# USB-PS2.net
KiCad netlist of a schematic drawn in EAGLE
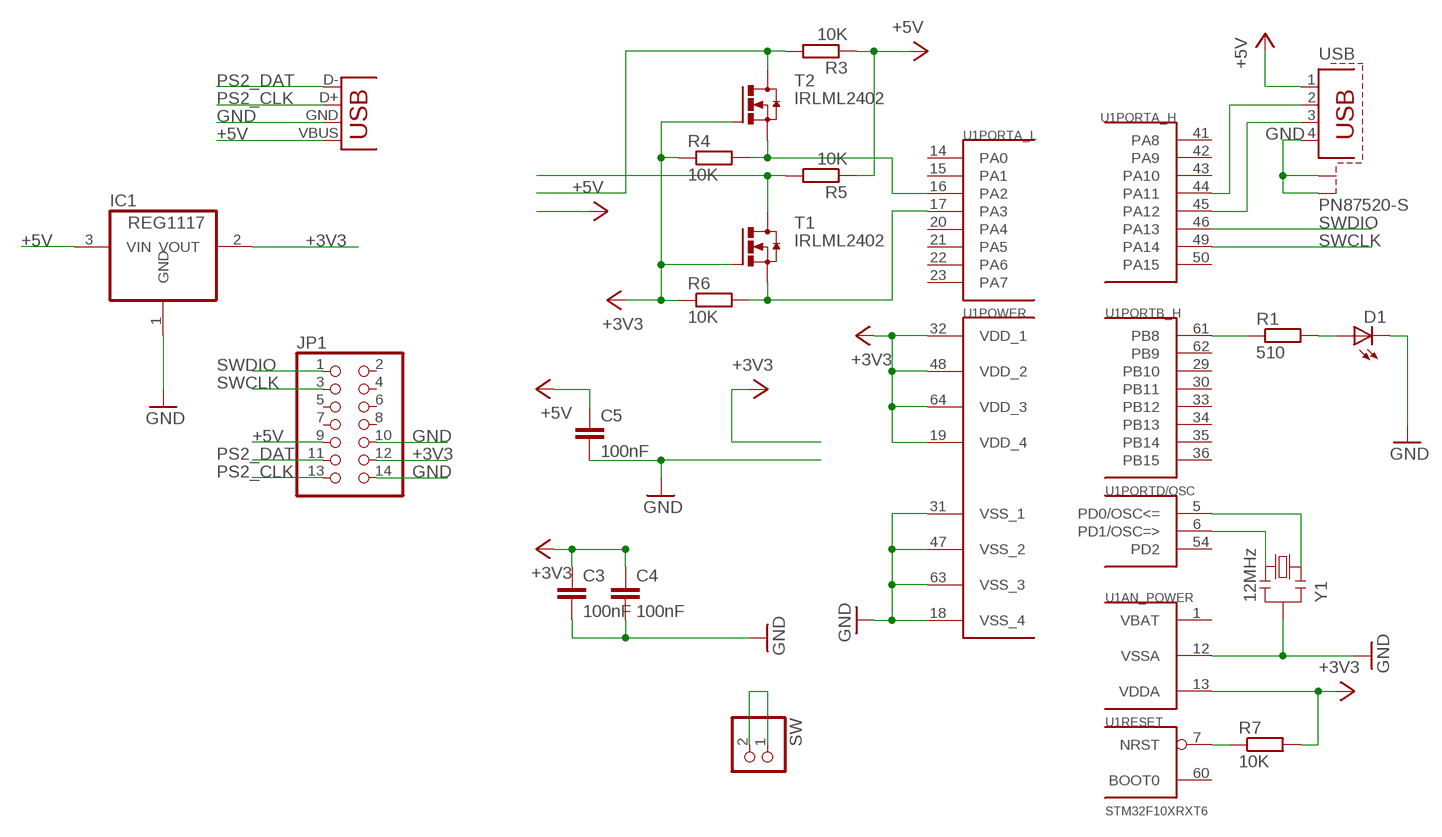
[diagram p0: schematic, sheet 1]

(export (version "E")
  (design (tool "Eeschema 10.0.6"))
  (components
    (comp (ref "C3")
      (value "100nF")
      (footprint "eagle-import:C0805")
      (libsource (lib "eagle-import") (part "C-EUC0805"))
    )
    (comp (ref "C4")
      (value "100nF")
      (footprint "eagle-import:C0805")
      (libsource (lib "eagle-import") (part "C-EUC0805"))
    )
    (comp (ref "C5")
      (value "100nF")
      (footprint "eagle-import:C0805")
      (libsource (lib "eagle-import") (part "C-EUC0805"))
    )
    (comp (ref "D1")
      (value "LEDSML0805")
      (footprint "eagle-import:SML0805")
      (libsource (lib "eagle-import") (part "LEDSML0805"))
    )
    (comp (ref "IC1")
      (value "REG1117")
      (footprint "eagle-import:SOT223")
      (libsource (lib "eagle-import") (part "REG1117"))
    )
    (comp (ref "JP1")
      (value "PINHD-2X7")
      (footprint "eagle-import:2X07")
      (libsource (lib "eagle-import") (part "PINHD-2X7"))
    )
    (comp (ref "R1")
      (value "510")
      (footprint "eagle-import:R0805")
      (libsource (lib "eagle-import") (part "R-EU_R0805"))
    )
    (comp (ref "R3")
      (value "10K")
      (footprint "eagle-import:R0805")
      (libsource (lib "eagle-import") (part "R-EU_R0805"))
    )
    (comp (ref "R4")
      (value "10K")
      (footprint "eagle-import:R0805")
      (libsource (lib "eagle-import") (part "R-EU_R0805"))
    )
    (comp (ref "R5")
      (value "10K")
      (footprint "eagle-import:R0805")
      (libsource (lib "eagle-import") (part "R-EU_R0805"))
    )
    (comp (ref "R6")
      (value "10K")
      (footprint "eagle-import:R0805")
      (libsource (lib "eagle-import") (part "R-EU_R0805"))
    )
    (comp (ref "R7")
      (value "10K")
      (footprint "eagle-import:R0805")
      (libsource (lib "eagle-import") (part "R-EU_R0805"))
    )
    (comp (ref "SW")
      (value "PINHD-1X2")
      (footprint "eagle-import:1X02")
      (libsource (lib "eagle-import") (part "PINHD-1X2"))
    )
    (comp (ref "T1")
      (value "IRLML2402")
      (footprint "eagle-import:MICRO3")
      (libsource (lib "eagle-import") (part "IRLML2402"))
    )
    (comp (ref "T2")
      (value "IRLML2402")
      (footprint "eagle-import:MICRO3")
      (libsource (lib "eagle-import") (part "IRLML2402"))
    )
    (comp (ref "U1")
      (value "STM32F10XRXT6")
      (footprint "eagle-import:TQFP64")
      (libsource (lib "eagle-import") (part "STM32F10XRXT6"))
    )
    (comp (ref "USB")
      (value "PN87520-S")
      (footprint "eagle-import:PN87520-S")
      (libsource (lib "eagle-import") (part "PN87520-S"))
    )
    (comp (ref "X1")
      (value "USB-A-H")
      (footprint "eagle-import:USB-A-H")
      (libsource (lib "eagle-import") (part "USB-A-H"))
    )
    (comp (ref "Y1")
      (value "12MHz")
      (footprint "eagle-import:RESONATOR")
      (fields (field (name "PART_NUMBER") "CSTCE16M0V53-R0"))
      (libsource (lib "eagle-import") (part "0011_CSTCE16M0V53-R0"))
    )
  )
  (nets
    (net (code "1") (name "+3V3") (class "Default")
      (node (ref "C3") (pin "1") (pinfunction "1_1") (pintype "passive"))
      (node (ref "C4") (pin "1") (pinfunction "1_1") (pintype "passive"))
      (node (ref "IC1") (pin "2") (pinfunction "VOUT_2") (pintype "output"))
      (node (ref "JP1") (pin "12") (pinfunction "12_12") (pintype "passive"))
      (node (ref "R4") (pin "1") (pinfunction "1_1") (pintype "passive"))
      (node (ref "R6") (pin "1") (pinfunction "1_1") (pintype "passive"))
      (node (ref "R7") (pin "2") (pinfunction "2_2") (pintype "passive"))
      (node (ref "T1") (pin "1") (pinfunction "G_1") (pintype "passive"))
      (node (ref "T2") (pin "1") (pinfunction "G_1") (pintype "passive"))
      (node (ref "U1") (pin "13") (pinfunction "VDDA_13") (pintype "power_in"))
      (node (ref "U1") (pin "19") (pinfunction "VDD_4_19") (pintype "power_in"))
      (node (ref "U1") (pin "32") (pinfunction "VDD_1_32") (pintype "power_in"))
      (node (ref "U1") (pin "48") (pinfunction "VDD_2_48") (pintype "power_in"))
      (node (ref "U1") (pin "64") (pinfunction "VDD_3_64") (pintype "power_in"))
    )
    (net (code "2") (name "+5V") (class "Default")
      (node (ref "C5") (pin "1") (pinfunction "1_1") (pintype "passive"))
      (node (ref "IC1") (pin "3") (pinfunction "VIN_3") (pintype "input"))
      (node (ref "JP1") (pin "9") (pinfunction "9_9") (pintype "passive"))
      (node (ref "R3") (pin "1") (pinfunction "1_1") (pintype "passive"))
      (node (ref "R5") (pin "1") (pinfunction "1_1") (pintype "passive"))
      (node (ref "USB") (pin "1") (pinfunction "1_1") (pintype "passive"))
      (node (ref "X1") (pin "VBUS") (pinfunction "GND_VBUS") (pintype "bidirectional"))
    )
    (net (code "3") (name "/PS2_CLK") (class "Default")
      (node (ref "JP1") (pin "13") (pinfunction "13_13") (pintype "passive"))
      (node (ref "R5") (pin "2") (pinfunction "2_2") (pintype "passive"))
      (node (ref "T1") (pin "3") (pinfunction "D_3") (pintype "passive"))
      (node (ref "X1") (pin "D+") (pinfunction "D-_D+") (pintype "bidirectional"))
    )
    (net (code "4") (name "/PS2_DAT") (class "Default")
      (node (ref "JP1") (pin "11") (pinfunction "11_11") (pintype "passive"))
      (node (ref "R3") (pin "2") (pinfunction "2_2") (pintype "passive"))
      (node (ref "T2") (pin "3") (pinfunction "D_3") (pintype "passive"))
      (node (ref "X1") (pin "D-") (pinfunction "D+_D-") (pintype "bidirectional"))
    )
    (net (code "5") (name "/SWCLK") (class "Default")
      (node (ref "JP1") (pin "3") (pinfunction "3_3") (pintype "passive"))
      (node (ref "U1") (pin "49") (pinfunction "PA14_49") (pintype "bidirectional"))
    )
    (net (code "6") (name "/SWDIO") (class "Default")
      (node (ref "JP1") (pin "1") (pinfunction "1_1") (pintype "passive"))
      (node (ref "U1") (pin "46") (pinfunction "PA13_46") (pintype "bidirectional"))
    )
    (net (code "7") (name "/VBAT") (class "Default")
      (node (ref "U1") (pin "1") (pinfunction "VBAT_1") (pintype "power_in"))
    )
    (net (code "8") (name "GND") (class "Default")
      (node (ref "C3") (pin "2") (pinfunction "2_2") (pintype "passive"))
      (node (ref "C4") (pin "2") (pinfunction "2_2") (pintype "passive"))
      (node (ref "C5") (pin "2") (pinfunction "2_2") (pintype "passive"))
      (node (ref "D1") (pin "C") (pinfunction "C_C") (pintype "passive"))
      (node (ref "IC1") (pin "1") (pinfunction "GND_1") (pintype "power_in"))
      (node (ref "JP1") (pin "10") (pinfunction "10_10") (pintype "passive"))
      (node (ref "JP1") (pin "14") (pinfunction "14_14") (pintype "passive"))
      (node (ref "U1") (pin "12") (pinfunction "VSSA_12") (pintype "power_in"))
      (node (ref "U1") (pin "18") (pinfunction "VSS_4_18") (pintype "power_in"))
      (node (ref "U1") (pin "31") (pinfunction "VSS_1_31") (pintype "power_in"))
      (node (ref "U1") (pin "47") (pinfunction "VSS_2_47") (pintype "power_in"))
      (node (ref "U1") (pin "63") (pinfunction "VSS_3_63") (pintype "power_in"))
      (node (ref "USB") (pin "4") (pinfunction "4_4") (pintype "passive"))
      (node (ref "USB") (pin "S1") (pinfunction "S1_S1") (pintype "passive"))
      (node (ref "USB") (pin "S2") (pinfunction "S2_S2") (pintype "passive"))
      (node (ref "X1") (pin "GND") (pinfunction "VBUS_GND") (pintype "bidirectional"))
      (node (ref "Y1") (pin "2") (pinfunction "2_2") (pintype "passive"))
    )
    (net (code "9") (name "Net-(D1-PadA)") (class "Default")
      (node (ref "D1") (pin "A") (pinfunction "A_A") (pintype "passive"))
      (node (ref "R1") (pin "2") (pinfunction "2_2") (pintype "passive"))
    )
    (net (code "10") (name "Net-(SW-Pad1)") (class "Default")
      (node (ref "SW") (pin "1") (pinfunction "1_1") (pintype "passive"))
      (node (ref "SW") (pin "2") (pinfunction "2_2") (pintype "passive"))
    )
    (net (code "11") (name "Net-(T1-S)") (class "Default")
      (node (ref "R6") (pin "2") (pinfunction "2_2") (pintype "passive"))
      (node (ref "T1") (pin "2") (pinfunction "S_2") (pintype "passive"))
      (node (ref "U1") (pin "17") (pinfunction "PA3_17") (pintype "bidirectional"))
    )
    (net (code "12") (name "Net-(T2-S)") (class "Default")
      (node (ref "R4") (pin "2") (pinfunction "2_2") (pintype "passive"))
      (node (ref "T2") (pin "2") (pinfunction "S_2") (pintype "passive"))
      (node (ref "U1") (pin "16") (pinfunction "PA2_16") (pintype "bidirectional"))
    )
    (net (code "13") (name "Net-(U1B-PA11)") (class "Default")
      (node (ref "U1") (pin "44") (pinfunction "PA11_44") (pintype "bidirectional"))
      (node (ref "USB") (pin "2") (pinfunction "2_2") (pintype "passive"))
    )
    (net (code "14") (name "Net-(U1B-PA12)") (class "Default")
      (node (ref "U1") (pin "45") (pinfunction "PA12_45") (pintype "bidirectional"))
      (node (ref "USB") (pin "3") (pinfunction "3_3") (pintype "passive"))
    )
    (net (code "15") (name "Net-(U1D-PB8)") (class "Default")
      (node (ref "R1") (pin "1") (pinfunction "1_1") (pintype "passive"))
      (node (ref "U1") (pin "61") (pinfunction "PB8_61") (pintype "bidirectional"))
    )
    (net (code "16") (name "Net-(U1H-PD0{slash}OSC<=)") (class "Default")
      (node (ref "U1") (pin "5") (pinfunction "PD0/OSC<=_5") (pintype "bidirectional"))
      (node (ref "Y1") (pin "1") (pinfunction "1_1") (pintype "passive"))
    )
    (net (code "17") (name "Net-(U1H-PD1{slash}OSC=>)") (class "Default")
      (node (ref "U1") (pin "6") (pinfunction "PD1/OSC=>_6") (pintype "bidirectional"))
      (node (ref "Y1") (pin "3") (pinfunction "3_3") (pintype "passive"))
    )
    (net (code "18") (name "Net-(U1J-NRST)") (class "Default")
      (node (ref "R7") (pin "1") (pinfunction "1_1") (pintype "passive"))
      (node (ref "U1") (pin "7") (pinfunction "NRST_7") (pintype "input"))
    )
    (net (code "19") (name "unconnected-(JP1-Pad2)") (class "Default")
      (node (ref "JP1") (pin "2") (pinfunction "2_2") (pintype "passive"))
    )
    (net (code "20") (name "unconnected-(JP1-Pad4)") (class "Default")
      (node (ref "JP1") (pin "4") (pinfunction "4_4") (pintype "passive"))
    )
    (net (code "21") (name "unconnected-(JP1-Pad5)") (class "Default")
      (node (ref "JP1") (pin "5") (pinfunction "5_5") (pintype "passive"))
    )
    (net (code "22") (name "unconnected-(JP1-Pad6)") (class "Default")
      (node (ref "JP1") (pin "6") (pinfunction "6_6") (pintype "passive"))
    )
    (net (code "23") (name "unconnected-(JP1-Pad7)") (class "Default")
      (node (ref "JP1") (pin "7") (pinfunction "7_7") (pintype "passive"))
    )
    (net (code "24") (name "unconnected-(JP1-Pad8)") (class "Default")
      (node (ref "JP1") (pin "8") (pinfunction "8_8") (pintype "passive"))
    )
    (net (code "25") (name "unconnected-(U1B-PA8-Pad41)") (class "Default")
      (node (ref "U1") (pin "41") (pinfunction "PA8_41") (pintype "bidirectional"))
    )
    (net (code "26") (name "unconnected-(U1B-PA9-Pad42)") (class "Default")
      (node (ref "U1") (pin "42") (pinfunction "PA9_42") (pintype "bidirectional"))
    )
    (net (code "27") (name "unconnected-(U1B-PA10-Pad43)") (class "Default")
      (node (ref "U1") (pin "43") (pinfunction "PA10_43") (pintype "bidirectional"))
    )
    (net (code "28") (name "unconnected-(U1B-PA15-Pad50)") (class "Default")
      (node (ref "U1") (pin "50") (pinfunction "PA15_50") (pintype "bidirectional"))
    )
    (net (code "29") (name "unconnected-(U1C-PA0-Pad14)") (class "Default")
      (node (ref "U1") (pin "14") (pinfunction "PA0_14") (pintype "bidirectional"))
    )
    (net (code "30") (name "unconnected-(U1C-PA1-Pad15)") (class "Default")
      (node (ref "U1") (pin "15") (pinfunction "PA1_15") (pintype "bidirectional"))
    )
    (net (code "31") (name "unconnected-(U1C-PA4-Pad20)") (class "Default")
      (node (ref "U1") (pin "20") (pinfunction "PA4_20") (pintype "bidirectional"))
    )
    (net (code "32") (name "unconnected-(U1C-PA5-Pad21)") (class "Default")
      (node (ref "U1") (pin "21") (pinfunction "PA5_21") (pintype "bidirectional"))
    )
    (net (code "33") (name "unconnected-(U1C-PA6-Pad22)") (class "Default")
      (node (ref "U1") (pin "22") (pinfunction "PA6_22") (pintype "bidirectional"))
    )
    (net (code "34") (name "unconnected-(U1C-PA7-Pad23)") (class "Default")
      (node (ref "U1") (pin "23") (pinfunction "PA7_23") (pintype "bidirectional"))
    )
    (net (code "35") (name "unconnected-(U1D-PB9-Pad62)") (class "Default")
      (node (ref "U1") (pin "62") (pinfunction "PB9_62") (pintype "bidirectional"))
    )
    (net (code "36") (name "unconnected-(U1D-PB10-Pad29)") (class "Default")
      (node (ref "U1") (pin "29") (pinfunction "PB10_29") (pintype "bidirectional"))
    )
    (net (code "37") (name "unconnected-(U1D-PB11-Pad30)") (class "Default")
      (node (ref "U1") (pin "30") (pinfunction "PB11_30") (pintype "bidirectional"))
    )
    (net (code "38") (name "unconnected-(U1D-PB12-Pad33)") (class "Default")
      (node (ref "U1") (pin "33") (pinfunction "PB12_33") (pintype "bidirectional"))
    )
    (net (code "39") (name "unconnected-(U1D-PB13-Pad34)") (class "Default")
      (node (ref "U1") (pin "34") (pinfunction "PB13_34") (pintype "bidirectional"))
    )
    (net (code "40") (name "unconnected-(U1D-PB14-Pad35)") (class "Default")
      (node (ref "U1") (pin "35") (pinfunction "PB14_35") (pintype "bidirectional"))
    )
    (net (code "41") (name "unconnected-(U1D-PB15-Pad36)") (class "Default")
      (node (ref "U1") (pin "36") (pinfunction "PB15_36") (pintype "bidirectional"))
    )
    (net (code "42") (name "unconnected-(U1H-PD2-Pad54)") (class "Default")
      (node (ref "U1") (pin "54") (pinfunction "PD2_54") (pintype "bidirectional"))
    )
    (net (code "43") (name "unconnected-(U1J-BOOT0-Pad60)") (class "Default")
      (node (ref "U1") (pin "60") (pinfunction "BOOT0_60") (pintype "input"))
    )
  )
)
